# R405H.net
KiCad netlist of a schematic drawn in EAGLE
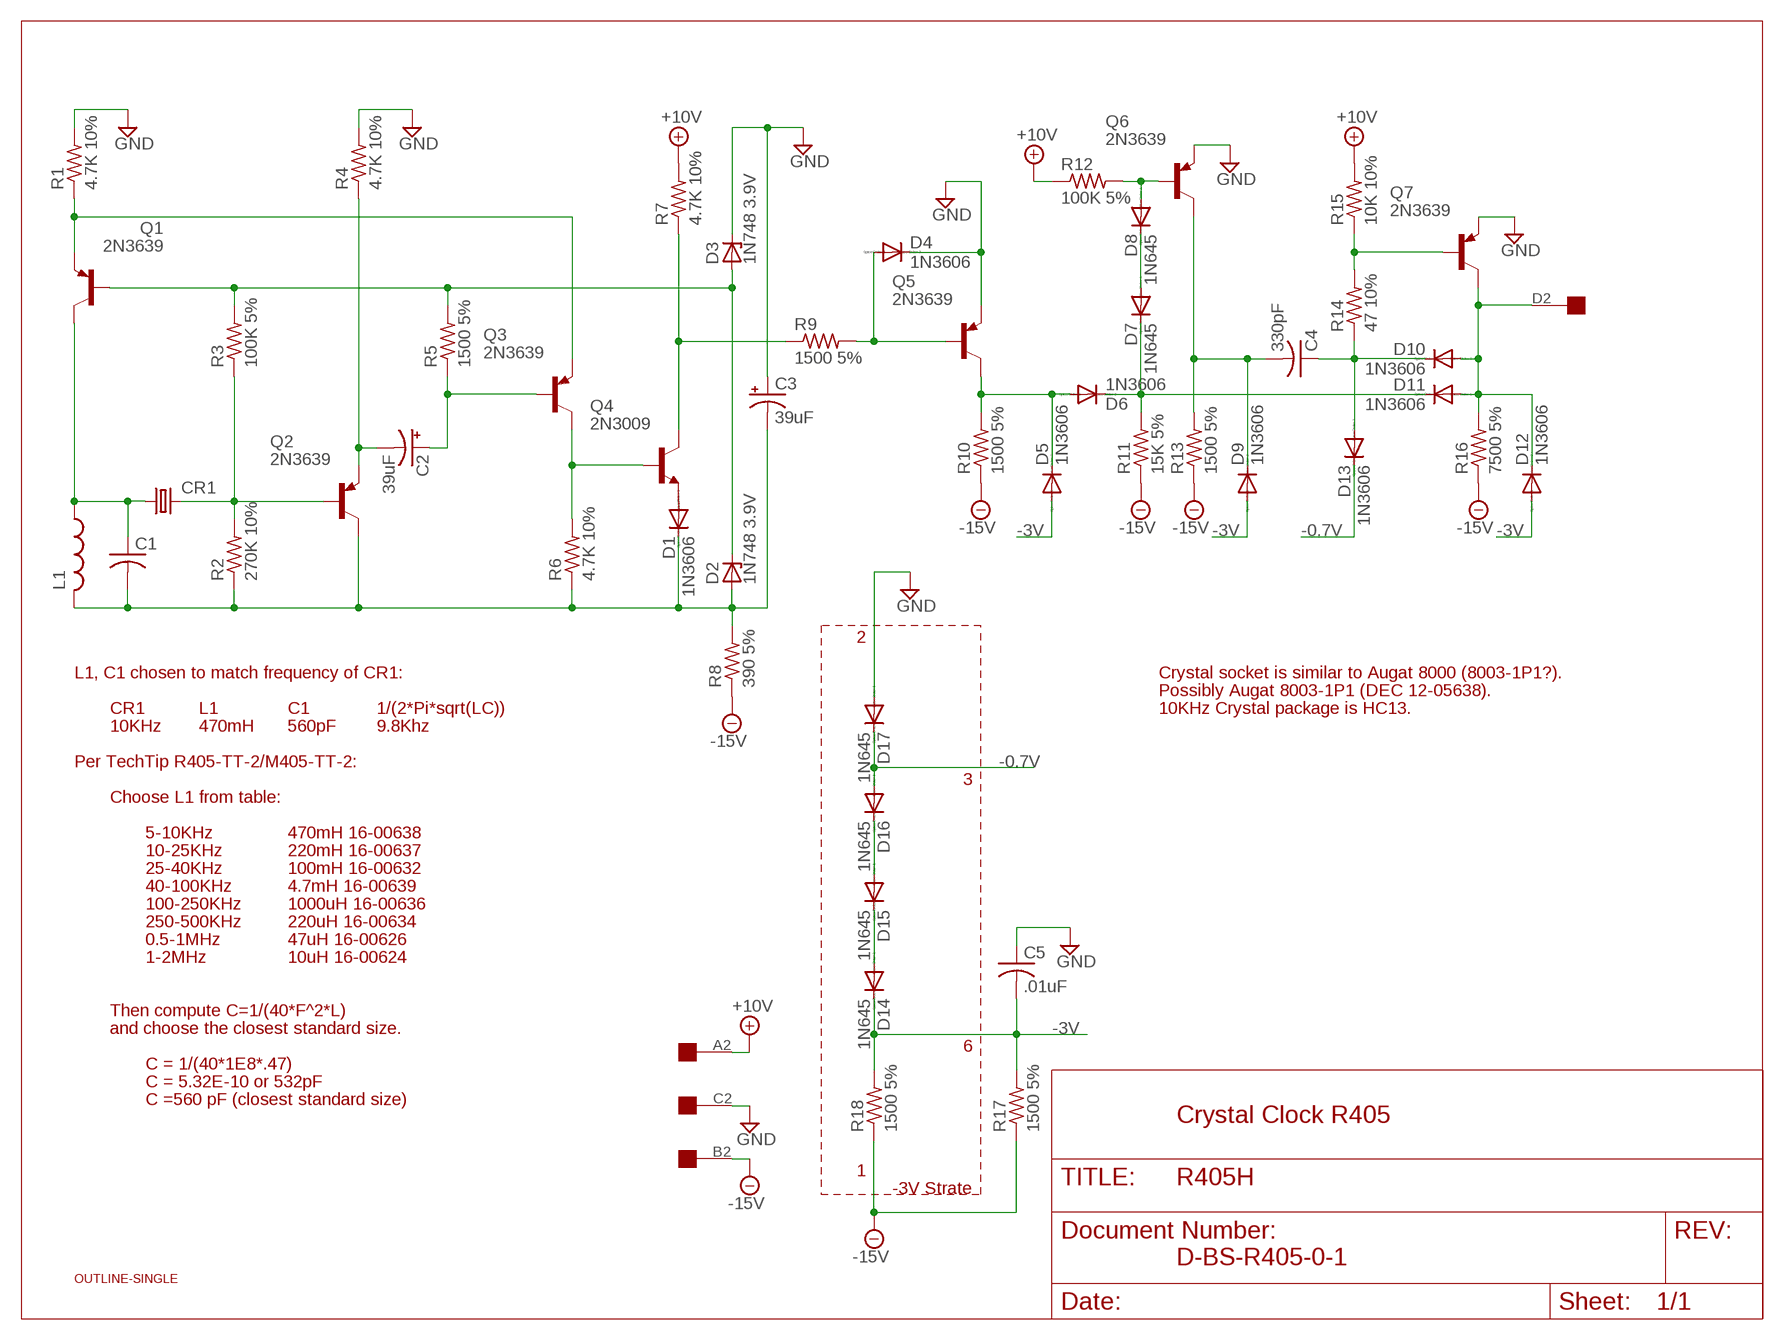
[diagram p0: schematic, sheet 1]

(export (version "E")
  (design (tool "Eeschema 10.0.6"))
  (components
    (comp (ref "C1")
      (value "C-US150-054X183")
      (footprint "eagle-import:C150-054X183")
      (libsource (lib "eagle-import") (part "C-US150-054X183"))
    )
    (comp (ref "C2")
      (value "39uF")
      (footprint "eagle-import:E15-5")
      (libsource (lib "eagle-import") (part "CPOL-USE15-5AXIAL"))
    )
    (comp (ref "C3")
      (value "39uF")
      (footprint "eagle-import:E15-5")
      (libsource (lib "eagle-import") (part "CPOL-USE15-5AXIAL"))
    )
    (comp (ref "C4")
      (value "330pF")
      (footprint "eagle-import:C150-054X183")
      (libsource (lib "eagle-import") (part "C-US150-054X183"))
    )
    (comp (ref "C5")
      (value ".01uF")
      (footprint "eagle-import:C150-054X183")
      (libsource (lib "eagle-import") (part "C-US150-054X183"))
    )
    (comp (ref "CR1")
      (value "CRYSTALHC13U-H")
      (footprint "eagle-import:HC13U-H")
      (libsource (lib "eagle-import") (part "CRYSTALHC13U-H"))
    )
    (comp (ref "D1")
      (value "1N3606")
      (footprint "eagle-import:DO35-10")
      (libsource (lib "eagle-import") (part "1N4148DO35-10"))
    )
    (comp (ref "D2")
      (value "1N748 3.9V")
      (footprint "eagle-import:DO35Z10")
      (libsource (lib "eagle-import") (part "ZENER-DIODEDO35Z10"))
    )
    (comp (ref "D3")
      (value "1N748 3.9V")
      (footprint "eagle-import:DO35Z10")
      (libsource (lib "eagle-import") (part "ZENER-DIODEDO35Z10"))
    )
    (comp (ref "D4")
      (value "1N3606")
      (footprint "eagle-import:DO35-10")
      (libsource (lib "eagle-import") (part "1N4148DO35-10"))
    )
    (comp (ref "D5")
      (value "1N3606")
      (footprint "eagle-import:DO35-10")
      (libsource (lib "eagle-import") (part "1N4148DO35-10"))
    )
    (comp (ref "D6")
      (value "1N3606")
      (footprint "eagle-import:DO35-10")
      (libsource (lib "eagle-import") (part "1N4148DO35-10"))
    )
    (comp (ref "D7")
      (value "1N645")
      (footprint "eagle-import:DO35-10")
      (libsource (lib "eagle-import") (part "1N4148DO35-10"))
    )
    (comp (ref "D8")
      (value "1N645")
      (footprint "eagle-import:DO35-10")
      (libsource (lib "eagle-import") (part "1N4148DO35-10"))
    )
    (comp (ref "D9")
      (value "1N3606")
      (footprint "eagle-import:DO35-10")
      (libsource (lib "eagle-import") (part "1N4148DO35-10"))
    )
    (comp (ref "D10")
      (value "1N3606")
      (footprint "eagle-import:DO35-10")
      (libsource (lib "eagle-import") (part "1N4148DO35-10"))
    )
    (comp (ref "D11")
      (value "1N3606")
      (footprint "eagle-import:DO35-10")
      (libsource (lib "eagle-import") (part "1N4148DO35-10"))
    )
    (comp (ref "D12")
      (value "1N3606")
      (footprint "eagle-import:DO35-10")
      (libsource (lib "eagle-import") (part "1N4148DO35-10"))
    )
    (comp (ref "D13")
      (value "1N3606")
      (footprint "eagle-import:DO35-10")
      (libsource (lib "eagle-import") (part "1N4148DO35-10"))
    )
    (comp (ref "D14")
      (value "1N645")
      (footprint "eagle-import:DO35-10")
      (libsource (lib "eagle-import") (part "1N4148DO35-10"))
    )
    (comp (ref "D15")
      (value "1N645")
      (footprint "eagle-import:DO35-10")
      (libsource (lib "eagle-import") (part "1N4148DO35-10"))
    )
    (comp (ref "D16")
      (value "1N645")
      (footprint "eagle-import:DO35-10")
      (libsource (lib "eagle-import") (part "1N4148DO35-10"))
    )
    (comp (ref "D17")
      (value "1N645")
      (footprint "eagle-import:DO35-10")
      (libsource (lib "eagle-import") (part "1N4148DO35-10"))
    )
    (comp (ref "L1")
      (value "L-US0207/7")
      (footprint "eagle-import:0207_7")
      (libsource (lib "eagle-import") (part "L-US0207/7"))
    )
    (comp (ref "Q1")
      (value "2N3639")
      (footprint "eagle-import:TO39")
      (libsource (lib "eagle-import") (part "2N2904"))
    )
    (comp (ref "Q2")
      (value "2N3639")
      (footprint "eagle-import:TO39")
      (libsource (lib "eagle-import") (part "2N2904"))
    )
    (comp (ref "Q3")
      (value "2N3639")
      (footprint "eagle-import:TO39")
      (libsource (lib "eagle-import") (part "2N2904"))
    )
    (comp (ref "Q4")
      (value "2N3009")
      (footprint "eagle-import:TO5")
      (libsource (lib "eagle-import") (part "2N2102"))
    )
    (comp (ref "Q5")
      (value "2N3639")
      (footprint "eagle-import:TO39")
      (libsource (lib "eagle-import") (part "2N2904"))
    )
    (comp (ref "Q6")
      (value "2N3639")
      (footprint "eagle-import:TO39")
      (libsource (lib "eagle-import") (part "2N2904"))
    )
    (comp (ref "Q7")
      (value "2N3639")
      (footprint "eagle-import:TO39")
      (libsource (lib "eagle-import") (part "2N2904"))
    )
    (comp (ref "R1")
      (value "4.7K 10%")
      (footprint "eagle-import:0207_10")
      (libsource (lib "eagle-import") (part "R-US_0207/10"))
    )
    (comp (ref "R2")
      (value "270K 10%")
      (footprint "eagle-import:0207_10")
      (libsource (lib "eagle-import") (part "R-US_0207/10"))
    )
    (comp (ref "R3")
      (value "100K 5%")
      (footprint "eagle-import:0207_10")
      (libsource (lib "eagle-import") (part "R-US_0207/10"))
    )
    (comp (ref "R4")
      (value "4.7K 10%")
      (footprint "eagle-import:0207_10")
      (libsource (lib "eagle-import") (part "R-US_0207/10"))
    )
    (comp (ref "R5")
      (value "1500 5%")
      (footprint "eagle-import:0207_10")
      (libsource (lib "eagle-import") (part "R-US_0207/10"))
    )
    (comp (ref "R6")
      (value "4.7K 10%")
      (footprint "eagle-import:0207_10")
      (libsource (lib "eagle-import") (part "R-US_0207/10"))
    )
    (comp (ref "R7")
      (value "4.7K 10%")
      (footprint "eagle-import:0207_10")
      (libsource (lib "eagle-import") (part "R-US_0207/10"))
    )
    (comp (ref "R8")
      (value "390 5%")
      (footprint "eagle-import:0207_10")
      (libsource (lib "eagle-import") (part "R-US_0207/10"))
    )
    (comp (ref "R9")
      (value "1500 5%")
      (footprint "eagle-import:0207_10")
      (libsource (lib "eagle-import") (part "R-US_0207/10"))
    )
    (comp (ref "R10")
      (value "1500 5%")
      (footprint "eagle-import:0207_10")
      (libsource (lib "eagle-import") (part "R-US_0207/10"))
    )
    (comp (ref "R11")
      (value "15K 5%")
      (footprint "eagle-import:0207_10")
      (libsource (lib "eagle-import") (part "R-US_0207/10"))
    )
    (comp (ref "R12")
      (value "100K 5%")
      (footprint "eagle-import:0207_10")
      (libsource (lib "eagle-import") (part "R-US_0207/10"))
    )
    (comp (ref "R13")
      (value "1500 5%")
      (footprint "eagle-import:0207_10")
      (libsource (lib "eagle-import") (part "R-US_0207/10"))
    )
    (comp (ref "R14")
      (value "47 10%")
      (footprint "eagle-import:0207_10")
      (libsource (lib "eagle-import") (part "R-US_0207/10"))
    )
    (comp (ref "R15")
      (value "10K 10%")
      (footprint "eagle-import:0207_10")
      (libsource (lib "eagle-import") (part "R-US_0207/10"))
    )
    (comp (ref "R16")
      (value "7500 5%")
      (footprint "eagle-import:0207_10")
      (libsource (lib "eagle-import") (part "R-US_0207/10"))
    )
    (comp (ref "R17")
      (value "1500 5%")
      (footprint "eagle-import:0207_10")
      (libsource (lib "eagle-import") (part "R-US_0207/10"))
    )
    (comp (ref "R18")
      (value "1500 5%")
      (footprint "eagle-import:0207_10")
      (libsource (lib "eagle-import") (part "R-US_0207/10"))
    )
    (comp (ref "U$1")
      (value "OUTLINE-SINGLE")
      (footprint "eagle-import:SINGLE")
      (libsource (lib "eagle-import") (part "OUTLINE-SINGLE"))
    )
    (comp (ref "U$2")
      (value "EDGE-1")
      (footprint "eagle-import:EDGE-CON1")
      (libsource (lib "eagle-import") (part "EDGE-1"))
    )
  )
  (nets
    (net (code "1") (name "+10V") (class "Default")
      (node (ref "R12") (pin "1") (pinfunction "1_1") (pintype "passive"))
      (node (ref "R15") (pin "2") (pinfunction "2_2") (pintype "passive"))
      (node (ref "R7") (pin "2") (pinfunction "2_2") (pintype "passive"))
      (node (ref "U$2") (pin "A2") (pinfunction "1_A2") (pintype "bidirectional"))
    )
    (net (code "2") (name "-15V") (class "Default")
      (node (ref "R10") (pin "1") (pinfunction "1_1") (pintype "passive"))
      (node (ref "R11") (pin "1") (pinfunction "1_1") (pintype "passive"))
      (node (ref "R13") (pin "1") (pinfunction "1_1") (pintype "passive"))
      (node (ref "R16") (pin "1") (pinfunction "1_1") (pintype "passive"))
      (node (ref "R17") (pin "1") (pinfunction "1_1") (pintype "passive"))
      (node (ref "R18") (pin "1") (pinfunction "1_1") (pintype "passive"))
      (node (ref "R8") (pin "1") (pinfunction "1_1") (pintype "passive"))
      (node (ref "U$2") (pin "B2") (pinfunction "1_B2") (pintype "bidirectional"))
    )
    (net (code "3") (name "/-0.7V") (class "Default")
      (node (ref "D13") (pin "C") (pinfunction "C_C") (pintype "passive"))
      (node (ref "D16") (pin "A") (pinfunction "A_A") (pintype "passive"))
      (node (ref "D17") (pin "C") (pinfunction "C_C") (pintype "passive"))
    )
    (net (code "4") (name "/-3V") (class "Default")
      (node (ref "C5") (pin "2") (pinfunction "2_2") (pintype "passive"))
      (node (ref "D12") (pin "A") (pinfunction "A_A") (pintype "passive"))
      (node (ref "D14") (pin "C") (pinfunction "C_C") (pintype "passive"))
      (node (ref "D5") (pin "A") (pinfunction "A_A") (pintype "passive"))
      (node (ref "D9") (pin "A") (pinfunction "A_A") (pintype "passive"))
      (node (ref "R17") (pin "2") (pinfunction "2_2") (pintype "passive"))
      (node (ref "R18") (pin "2") (pinfunction "2_2") (pintype "passive"))
    )
    (net (code "5") (name "GND") (class "Default")
      (node (ref "C3") (pin "+") (pinfunction "+_+") (pintype "passive"))
      (node (ref "C5") (pin "1") (pinfunction "1_1") (pintype "passive"))
      (node (ref "D17") (pin "A") (pinfunction "A_A") (pintype "passive"))
      (node (ref "D3") (pin "C") (pinfunction "C_C") (pintype "passive"))
      (node (ref "D4") (pin "C") (pinfunction "C_C") (pintype "passive"))
      (node (ref "Q5") (pin "1") (pinfunction "E_1") (pintype "passive"))
      (node (ref "Q6") (pin "1") (pinfunction "E_1") (pintype "passive"))
      (node (ref "Q7") (pin "1") (pinfunction "E_1") (pintype "passive"))
      (node (ref "R1") (pin "2") (pinfunction "2_2") (pintype "passive"))
      (node (ref "R4") (pin "2") (pinfunction "2_2") (pintype "passive"))
      (node (ref "U$2") (pin "C2") (pinfunction "1_C2") (pintype "bidirectional"))
    )
    (net (code "6") (name "Net-(C4-Pad1)") (class "Default")
      (node (ref "C4") (pin "1") (pinfunction "1_1") (pintype "passive"))
      (node (ref "D10") (pin "C") (pinfunction "C_C") (pintype "passive"))
      (node (ref "D13") (pin "A") (pinfunction "A_A") (pintype "passive"))
      (node (ref "R14") (pin "1") (pinfunction "1_1") (pintype "passive"))
    )
    (net (code "7") (name "Net-(D7-PadA)") (class "Default")
      (node (ref "D7") (pin "A") (pinfunction "A_A") (pintype "passive"))
      (node (ref "D8") (pin "C") (pinfunction "C_C") (pintype "passive"))
    )
    (net (code "8") (name "Net-(D11-PadC)") (class "Default")
      (node (ref "D11") (pin "C") (pinfunction "C_C") (pintype "passive"))
      (node (ref "D6") (pin "C") (pinfunction "C_C") (pintype "passive"))
      (node (ref "D7") (pin "C") (pinfunction "C_C") (pintype "passive"))
      (node (ref "R11") (pin "2") (pinfunction "2_2") (pintype "passive"))
    )
    (net (code "9") (name "Net-(D14-PadA)") (class "Default")
      (node (ref "D14") (pin "A") (pinfunction "A_A") (pintype "passive"))
      (node (ref "D15") (pin "C") (pinfunction "C_C") (pintype "passive"))
    )
    (net (code "10") (name "Net-(D15-PadA)") (class "Default")
      (node (ref "D15") (pin "A") (pinfunction "A_A") (pintype "passive"))
      (node (ref "D16") (pin "C") (pinfunction "C_C") (pintype "passive"))
    )
    (net (code "11") (name "Net-(Q1-B)") (class "Default")
      (node (ref "D2") (pin "C") (pinfunction "C_C") (pintype "passive"))
      (node (ref "D3") (pin "A") (pinfunction "A_A") (pintype "passive"))
      (node (ref "Q1") (pin "2") (pinfunction "B_2") (pintype "passive"))
      (node (ref "R3") (pin "2") (pinfunction "2_2") (pintype "passive"))
      (node (ref "R5") (pin "2") (pinfunction "2_2") (pintype "passive"))
    )
    (net (code "12") (name "Net-(Q1-C)") (class "Default")
      (node (ref "C1") (pin "1") (pinfunction "1_1") (pintype "passive"))
      (node (ref "CR1") (pin "1") (pinfunction "1_1") (pintype "passive"))
      (node (ref "L1") (pin "1") (pinfunction "1_1") (pintype "passive"))
      (node (ref "Q1") (pin "3") (pinfunction "C_3") (pintype "passive"))
    )
    (net (code "13") (name "Net-(Q1-E)") (class "Default")
      (node (ref "Q1") (pin "1") (pinfunction "E_1") (pintype "passive"))
      (node (ref "Q3") (pin "1") (pinfunction "E_1") (pintype "passive"))
      (node (ref "R1") (pin "1") (pinfunction "1_1") (pintype "passive"))
    )
    (net (code "14") (name "Net-(Q2-B)") (class "Default")
      (node (ref "CR1") (pin "2") (pinfunction "2_2") (pintype "passive"))
      (node (ref "Q2") (pin "2") (pinfunction "B_2") (pintype "passive"))
      (node (ref "R2") (pin "2") (pinfunction "2_2") (pintype "passive"))
      (node (ref "R3") (pin "1") (pinfunction "1_1") (pintype "passive"))
    )
    (net (code "15") (name "Net-(Q2-C)") (class "Default")
      (node (ref "C1") (pin "2") (pinfunction "2_2") (pintype "passive"))
      (node (ref "C3") (pin "-") (pinfunction "-_-") (pintype "passive"))
      (node (ref "D1") (pin "C") (pinfunction "C_C") (pintype "passive"))
      (node (ref "D2") (pin "A") (pinfunction "A_A") (pintype "passive"))
      (node (ref "L1") (pin "2") (pinfunction "2_2") (pintype "passive"))
      (node (ref "Q2") (pin "3") (pinfunction "C_3") (pintype "passive"))
      (node (ref "R2") (pin "1") (pinfunction "1_1") (pintype "passive"))
      (node (ref "R6") (pin "1") (pinfunction "1_1") (pintype "passive"))
      (node (ref "R8") (pin "2") (pinfunction "2_2") (pintype "passive"))
    )
    (net (code "16") (name "Net-(Q2-E)") (class "Default")
      (node (ref "C2") (pin "-") (pinfunction "-_-") (pintype "passive"))
      (node (ref "Q2") (pin "1") (pinfunction "E_1") (pintype "passive"))
      (node (ref "R4") (pin "1") (pinfunction "1_1") (pintype "passive"))
    )
    (net (code "17") (name "Net-(Q3-B)") (class "Default")
      (node (ref "C2") (pin "+") (pinfunction "+_+") (pintype "passive"))
      (node (ref "Q3") (pin "2") (pinfunction "B_2") (pintype "passive"))
      (node (ref "R5") (pin "1") (pinfunction "1_1") (pintype "passive"))
    )
    (net (code "18") (name "Net-(Q3-C)") (class "Default")
      (node (ref "Q3") (pin "3") (pinfunction "C_3") (pintype "passive"))
      (node (ref "Q4") (pin "2") (pinfunction "B_2") (pintype "passive"))
      (node (ref "R6") (pin "2") (pinfunction "2_2") (pintype "passive"))
    )
    (net (code "19") (name "Net-(Q4-C)") (class "Default")
      (node (ref "Q4") (pin "3") (pinfunction "C_3") (pintype "passive"))
      (node (ref "R7") (pin "1") (pinfunction "1_1") (pintype "passive"))
      (node (ref "R9") (pin "1") (pinfunction "1_1") (pintype "passive"))
    )
    (net (code "20") (name "Net-(Q4-E)") (class "Default")
      (node (ref "D1") (pin "A") (pinfunction "A_A") (pintype "passive"))
      (node (ref "Q4") (pin "1") (pinfunction "E_1") (pintype "passive"))
    )
    (net (code "21") (name "Net-(Q5-B)") (class "Default")
      (node (ref "D4") (pin "A") (pinfunction "A_A") (pintype "passive"))
      (node (ref "Q5") (pin "2") (pinfunction "B_2") (pintype "passive"))
      (node (ref "R9") (pin "2") (pinfunction "2_2") (pintype "passive"))
    )
    (net (code "22") (name "Net-(Q5-C)") (class "Default")
      (node (ref "D5") (pin "C") (pinfunction "C_C") (pintype "passive"))
      (node (ref "D6") (pin "A") (pinfunction "A_A") (pintype "passive"))
      (node (ref "Q5") (pin "3") (pinfunction "C_3") (pintype "passive"))
      (node (ref "R10") (pin "2") (pinfunction "2_2") (pintype "passive"))
    )
    (net (code "23") (name "Net-(Q6-B)") (class "Default")
      (node (ref "D8") (pin "A") (pinfunction "A_A") (pintype "passive"))
      (node (ref "Q6") (pin "2") (pinfunction "B_2") (pintype "passive"))
      (node (ref "R12") (pin "2") (pinfunction "2_2") (pintype "passive"))
    )
    (net (code "24") (name "Net-(Q6-C)") (class "Default")
      (node (ref "C4") (pin "2") (pinfunction "2_2") (pintype "passive"))
      (node (ref "D9") (pin "C") (pinfunction "C_C") (pintype "passive"))
      (node (ref "Q6") (pin "3") (pinfunction "C_3") (pintype "passive"))
      (node (ref "R13") (pin "2") (pinfunction "2_2") (pintype "passive"))
    )
    (net (code "25") (name "Net-(Q7-B)") (class "Default")
      (node (ref "Q7") (pin "2") (pinfunction "B_2") (pintype "passive"))
      (node (ref "R14") (pin "2") (pinfunction "2_2") (pintype "passive"))
      (node (ref "R15") (pin "1") (pinfunction "1_1") (pintype "passive"))
    )
    (net (code "26") (name "Net-(Q7-C)") (class "Default")
      (node (ref "D10") (pin "A") (pinfunction "A_A") (pintype "passive"))
      (node (ref "D11") (pin "A") (pinfunction "A_A") (pintype "passive"))
      (node (ref "D12") (pin "C") (pinfunction "C_C") (pintype "passive"))
      (node (ref "Q7") (pin "3") (pinfunction "C_3") (pintype "passive"))
      (node (ref "R16") (pin "2") (pinfunction "2_2") (pintype "passive"))
      (node (ref "U$2") (pin "D2") (pinfunction "1_D2") (pintype "bidirectional"))
    )
  )
)
